# design.net
KiCad netlist of a schematic drawn in Altium Designer
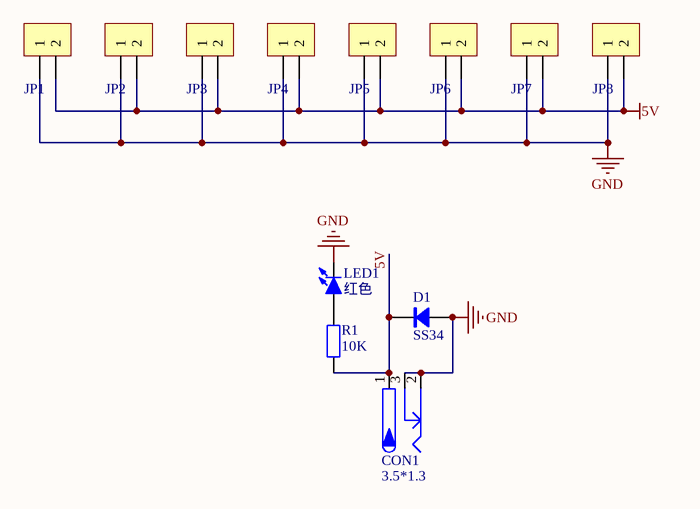
[diagram p0: 电源板.SchDoc]

(export (version "E")
  (design (tool "Eeschema 10.0.6"))
  (components
    (comp (ref "CON1")
      (value "3.5*1.3")
      (footprint "DC-005")
      (description "低压电源接口")
      (fields (field (name "版权归属") "源创客"))
      (libsource (lib "接口类") (part "P-DC"))
    )
    (comp (ref "D1")
      (value "SS34")
      (footprint "SMA")
      (description "肖特基二极管")
      (fields (field (name "版权归属") "源创客"))
      (libsource (lib "二极管-整流桥") (part "SS54"))
    )
    (comp (ref "JP1")
      (value "HDR-1X2")
      (footprint "HT3.96-WI-2P")
      (description "2P接插件")
      (fields (field (name "版权归属") "封装库来自淘宝卖家 ID：黄晶宝石"))
      (libsource (lib "5.6  - 接插件-脚距3.96") (part "Header 2"))
    )
    (comp (ref "JP2")
      (value "HDR-1X2")
      (footprint "HT3.96-WI-2P")
      (description "2P接插件")
      (fields (field (name "版权归属") "封装库来自淘宝卖家 ID：黄晶宝石"))
      (libsource (lib "5.6  - 接插件-脚距3.96") (part "Header 2"))
    )
    (comp (ref "JP3")
      (value "HDR-1X2")
      (footprint "HT3.96-WI-2P")
      (description "2P接插件")
      (fields (field (name "版权归属") "封装库来自淘宝卖家 ID：黄晶宝石"))
      (libsource (lib "5.6  - 接插件-脚距3.96") (part "Header 2"))
    )
    (comp (ref "JP4")
      (value "HDR-1X2")
      (footprint "HT3.96-WI-2P")
      (description "2P接插件")
      (fields (field (name "版权归属") "封装库来自淘宝卖家 ID：黄晶宝石"))
      (libsource (lib "5.6  - 接插件-脚距3.96") (part "Header 2"))
    )
    (comp (ref "JP5")
      (value "HDR-1X2")
      (footprint "HT3.96-WI-2P")
      (description "2P接插件")
      (fields (field (name "版权归属") "封装库来自淘宝卖家 ID：黄晶宝石"))
      (libsource (lib "5.6  - 接插件-脚距3.96") (part "Header 2"))
    )
    (comp (ref "JP6")
      (value "HDR-1X2")
      (footprint "HT3.96-WI-2P")
      (description "2P接插件")
      (fields (field (name "版权归属") "封装库来自淘宝卖家 ID：黄晶宝石"))
      (libsource (lib "5.6  - 接插件-脚距3.96") (part "Header 2"))
    )
    (comp (ref "JP7")
      (value "HDR-1X2")
      (footprint "HT3.96-WI-2P")
      (description "2P接插件")
      (fields (field (name "版权归属") "封装库来自淘宝卖家 ID：黄晶宝石"))
      (libsource (lib "5.6  - 接插件-脚距3.96") (part "Header 2"))
    )
    (comp (ref "JP8")
      (value "HDR-1X2")
      (footprint "HT3.96-WI-2P")
      (description "2P接插件")
      (fields (field (name "版权归属") "封装库来自淘宝卖家 ID：黄晶宝石"))
      (libsource (lib "5.6  - 接插件-脚距3.96") (part "Header 2"))
    )
    (comp (ref "LED1")
      (value "红色")
      (footprint "LED 0805R")
      (description "贴片LED")
      (fields (field (name "版权归属") "封装库来自淘宝 ID：黄晶宝石"))
      (libsource (lib "0.3 - LED发光二极管") (part "LED-SMD"))
    )
    (comp (ref "R1")
      (value "10K")
      (footprint "R 0805_L")
      (description "贴片电阻")
      (fields (field (name "版权归属") "来自淘宝 ID：黄晶宝石"))
      (libsource (lib "0.1 - 电阻-电容-电感") (part "R"))
    )
  )
  (nets
    (net (code "1") (name "5V") (class "Default")
      (node (ref "CON1") (pin "1") (pintype "power_in"))
      (node (ref "D1") (pin "2") (pinfunction "K_2") (pintype "passive"))
      (node (ref "JP1") (pin "2") (pinfunction "2_2") (pintype "passive"))
      (node (ref "JP2") (pin "2") (pinfunction "2_2") (pintype "passive"))
      (node (ref "JP3") (pin "2") (pinfunction "2_2") (pintype "passive"))
      (node (ref "JP4") (pin "2") (pinfunction "2_2") (pintype "passive"))
      (node (ref "JP5") (pin "2") (pinfunction "2_2") (pintype "passive"))
      (node (ref "JP6") (pin "2") (pinfunction "2_2") (pintype "passive"))
      (node (ref "JP7") (pin "2") (pinfunction "2_2") (pintype "passive"))
      (node (ref "JP8") (pin "2") (pinfunction "2_2") (pintype "passive"))
      (node (ref "R1") (pin "1") (pinfunction "1_1") (pintype "passive"))
    )
    (net (code "2") (name "GND") (class "Default")
      (node (ref "CON1") (pin "2") (pintype "power_in"))
      (node (ref "CON1") (pin "3") (pintype "power_in"))
      (node (ref "D1") (pin "1") (pinfunction "A_1") (pintype "passive"))
      (node (ref "JP1") (pin "1") (pinfunction "1_1") (pintype "passive"))
      (node (ref "JP2") (pin "1") (pinfunction "1_1") (pintype "passive"))
      (node (ref "JP3") (pin "1") (pinfunction "1_1") (pintype "passive"))
      (node (ref "JP4") (pin "1") (pinfunction "1_1") (pintype "passive"))
      (node (ref "JP5") (pin "1") (pinfunction "1_1") (pintype "passive"))
      (node (ref "JP6") (pin "1") (pinfunction "1_1") (pintype "passive"))
      (node (ref "JP7") (pin "1") (pinfunction "1_1") (pintype "passive"))
      (node (ref "JP8") (pin "1") (pinfunction "1_1") (pintype "passive"))
      (node (ref "LED1") (pin "2") (pinfunction "K_2") (pintype "passive"))
    )
    (net (code "3") (name "Net-(LED1-A)") (class "Default")
      (node (ref "LED1") (pin "1") (pinfunction "A_1") (pintype "passive"))
      (node (ref "R1") (pin "2") (pinfunction "2_2") (pintype "passive"))
    )
  )
)
